# design.net
KiCad netlist of a schematic drawn in Altium Designer
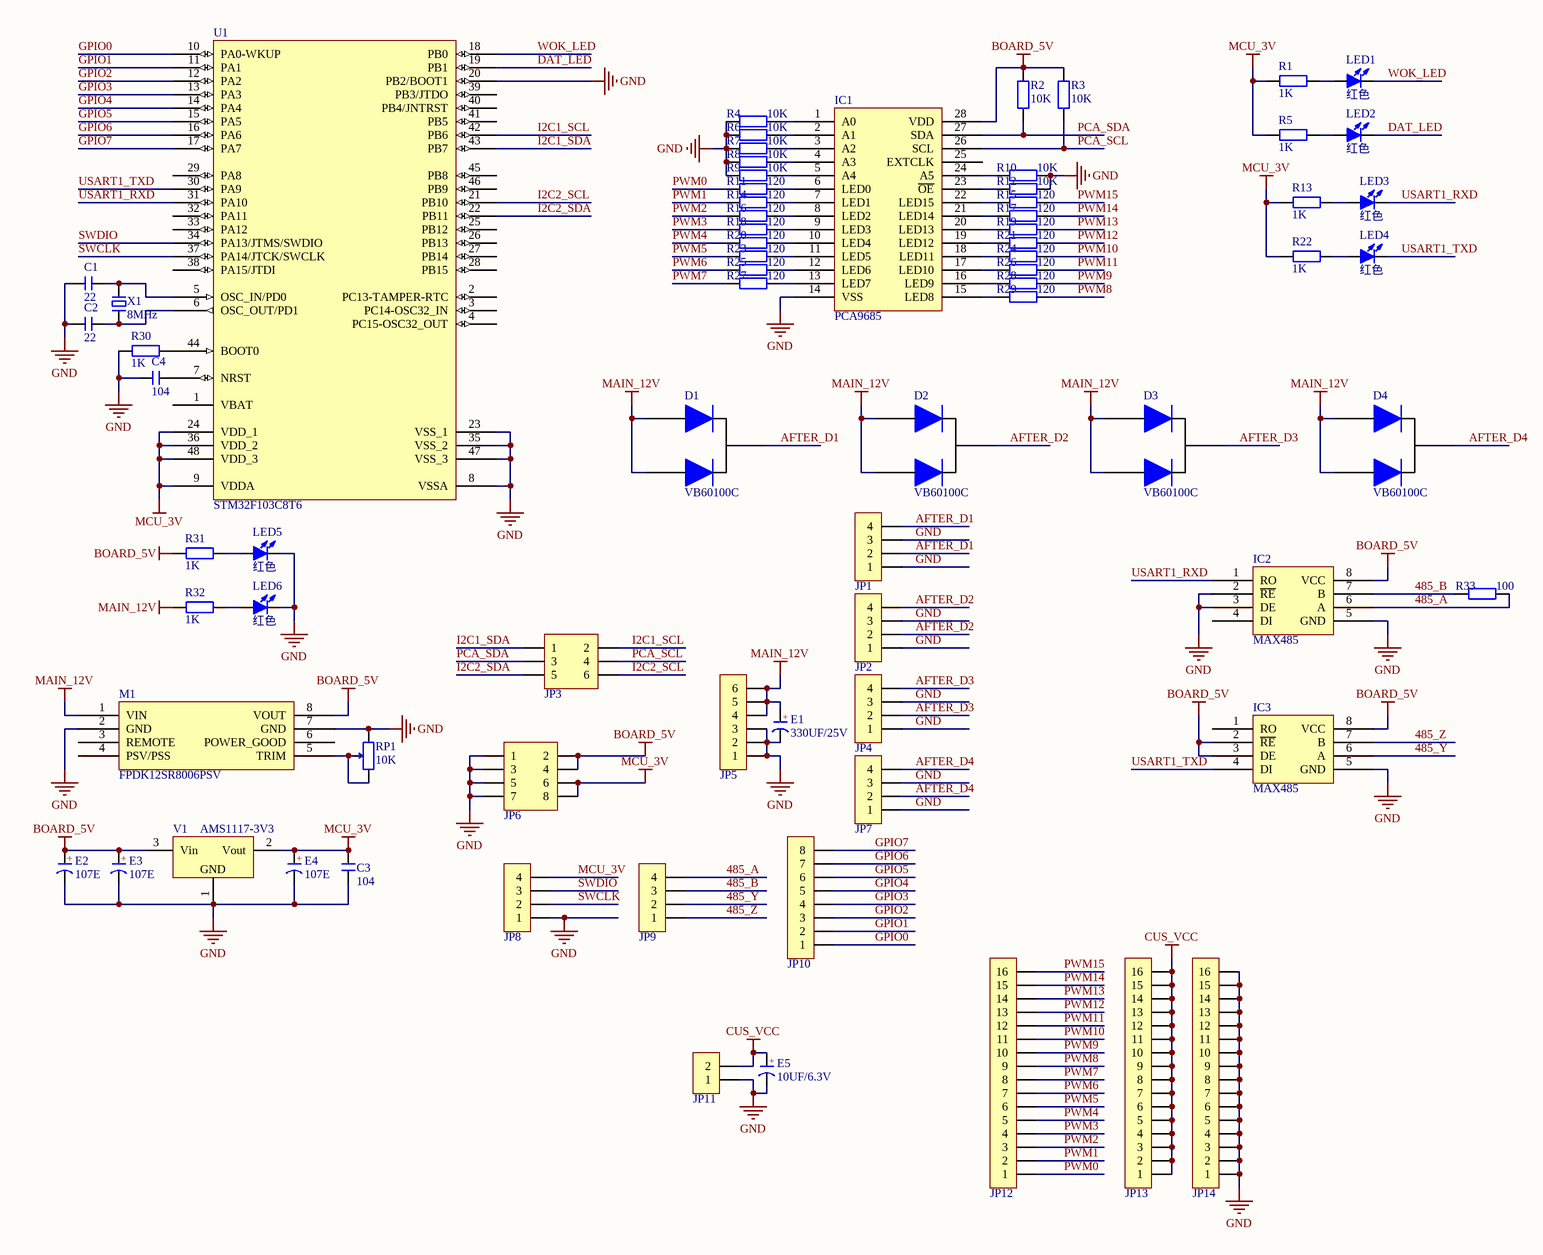
[diagram p0: 电源舱控制板.SchDoc]

(export (version "E")
  (design (tool "Eeschema 10.0.6"))
  (components
    (comp (ref "C1") (value "22") (description "无极性贴片电容") (libsource (lib "电阻-电容-电感") (part "C")))
    (comp (ref "C2") (value "22") (description "无极性贴片电容") (libsource (lib "电阻-电容-电感") (part "C")))
    (comp (ref "C3") (value "104") (description "无极性贴片电容") (libsource (lib "电阻-电容-电感") (part "C")))
    (comp (ref "C4") (value "104") (description "无极性贴片电容") (libsource (lib "电阻-电容-电感") (part "C")))
    (comp (ref "D1")
      (value "VB60100C")
      (description "60A 100V 肖特基势垒二极管")
      (libsource (lib "ROV") (part "VB60100C"))
    )
    (comp (ref "D2")
      (value "VB60100C")
      (description "60A 100V 肖特基势垒二极管")
      (libsource (lib "ROV") (part "VB60100C"))
    )
    (comp (ref "D3")
      (value "VB60100C")
      (description "60A 100V 肖特基势垒二极管")
      (libsource (lib "ROV") (part "VB60100C"))
    )
    (comp (ref "D4")
      (value "VB60100C")
      (description "60A 100V 肖特基势垒二极管")
      (libsource (lib "ROV") (part "VB60100C"))
    )
    (comp (ref "E1") (value "330UF/25V") (description "直插固态电容") (libsource (lib "电阻-电容-电感") (part "C-CS")))
    (comp (ref "E2") (value "107E") (description "贴片钽电容") (libsource (lib "电阻-电容-电感") (part "C-CD")))
    (comp (ref "E3") (value "107E") (description "贴片钽电容") (libsource (lib "电阻-电容-电感") (part "C-CD")))
    (comp (ref "E4") (value "107E") (description "贴片钽电容") (libsource (lib "电阻-电容-电感") (part "C-CD")))
    (comp (ref "E5") (value "10UF/6.3V") (description "直插固态电容") (libsource (lib "电阻-电容-电感") (part "C-CS")))
    (comp (ref "IC1") (value "PCA9685") (libsource (lib "ROV") (part "PCA9685")))
    (comp (ref "IC2") (value "MAX485") (description "485通信芯片") (libsource (lib "ROV") (part "MAX485")))
    (comp (ref "IC3") (value "MAX485") (description "485通信芯片") (libsource (lib "ROV") (part "MAX485")))
    (comp (ref "JP1") (value "HDR-1X4") (description "4P接插件") (libsource (lib "接插件") (part "Header 4")))
    (comp (ref "JP2") (value "HDR-1X4") (description "4P接插件") (libsource (lib "接插件") (part "Header 4")))
    (comp (ref "JP3") (value "Header3X2") (description "3*2P接插件") (libsource (lib "接插件") (part "Header 3X2")))
    (comp (ref "JP4") (value "HDR-1X4") (description "4P接插件") (libsource (lib "接插件") (part "Header 4")))
    (comp (ref "JP5") (value "HDR-1X6") (description "6P接插件") (libsource (lib "接插件") (part "Header 6")))
    (comp (ref "JP6")
      (value "Header 4X2")
      (description "4*2P接插件")
      (libsource (lib "接插件") (part "Header 4X2"))
    )
    (comp (ref "JP7") (value "HDR-1X4") (description "4P接插件") (libsource (lib "接插件") (part "Header 4")))
    (comp (ref "JP8") (value "HDR-1X4") (description "4P接插件") (libsource (lib "接插件") (part "Header 4")))
    (comp (ref "JP9") (value "HDR-1X4") (description "4P接插件") (libsource (lib "接插件") (part "Header 4")))
    (comp (ref "JP10") (value "HDR-1X8") (description "8P接插件") (libsource (lib "接插件") (part "Header 8")))
    (comp (ref "JP11") (value "HDR-1X2") (description "2P接插件") (libsource (lib "接插件") (part "Header 2")))
    (comp (ref "JP12") (value "HDR-1X16") (description "16P接插件") (libsource (lib "接插件") (part "Header 16")))
    (comp (ref "JP13") (value "HDR-1X16") (description "16P接插件") (libsource (lib "接插件") (part "Header 16")))
    (comp (ref "JP14") (value "HDR-1X16") (description "16P接插件") (libsource (lib "接插件") (part "Header 16")))
    (comp (ref "LED1") (value "红色") (description "贴片LED") (libsource (lib "LED") (part "LED-SMD")))
    (comp (ref "LED2") (value "红色") (description "贴片LED") (libsource (lib "LED") (part "LED-SMD")))
    (comp (ref "LED3") (value "红色") (description "贴片LED") (libsource (lib "LED") (part "LED-SMD")))
    (comp (ref "LED4") (value "红色") (description "贴片LED") (libsource (lib "LED") (part "LED-SMD")))
    (comp (ref "LED5") (value "红色") (description "贴片LED") (libsource (lib "LED") (part "LED-SMD")))
    (comp (ref "LED6") (value "红色") (description "贴片LED") (libsource (lib "LED") (part "LED-SMD")))
    (comp (ref "M1")
      (value "FPDK12SR8006PSV")
      (footprint "FPDK12SR8006PSV")
      (description "DC-DC POWER CONVERTOR 12V-TO-5V")
      (libsource (lib "ROV") (part "FPDK12SR8006PSV"))
    )
    (comp (ref "R1") (value "1K") (description "贴片电阻") (libsource (lib "电阻-电容-电感") (part "R")))
    (comp (ref "R2") (value "10K") (description "贴片电阻") (libsource (lib "电阻-电容-电感") (part "R")))
    (comp (ref "R3") (value "10K") (description "贴片电阻") (libsource (lib "电阻-电容-电感") (part "R")))
    (comp (ref "R4") (value "10K") (description "贴片电阻") (libsource (lib "电阻-电容-电感") (part "R")))
    (comp (ref "R5") (value "1K") (description "贴片电阻") (libsource (lib "电阻-电容-电感") (part "R")))
    (comp (ref "R6") (value "10K") (description "贴片电阻") (libsource (lib "电阻-电容-电感") (part "R")))
    (comp (ref "R7") (value "10K") (description "贴片电阻") (libsource (lib "电阻-电容-电感") (part "R")))
    (comp (ref "R8") (value "10K") (description "贴片电阻") (libsource (lib "电阻-电容-电感") (part "R")))
    (comp (ref "R9") (value "10K") (description "贴片电阻") (libsource (lib "电阻-电容-电感") (part "R")))
    (comp (ref "R10") (value "10K") (description "贴片电阻") (libsource (lib "电阻-电容-电感") (part "R")))
    (comp (ref "R11") (value "120") (description "贴片电阻") (libsource (lib "电阻-电容-电感") (part "R")))
    (comp (ref "R12") (value "10K") (description "贴片电阻") (libsource (lib "电阻-电容-电感") (part "R")))
    (comp (ref "R13") (value "1K") (description "贴片电阻") (libsource (lib "电阻-电容-电感") (part "R")))
    (comp (ref "R14") (value "120") (description "贴片电阻") (libsource (lib "电阻-电容-电感") (part "R")))
    (comp (ref "R15") (value "120") (description "贴片电阻") (libsource (lib "电阻-电容-电感") (part "R")))
    (comp (ref "R16") (value "120") (description "贴片电阻") (libsource (lib "电阻-电容-电感") (part "R")))
    (comp (ref "R17") (value "120") (description "贴片电阻") (libsource (lib "电阻-电容-电感") (part "R")))
    (comp (ref "R18") (value "120") (description "贴片电阻") (libsource (lib "电阻-电容-电感") (part "R")))
    (comp (ref "R19") (value "120") (description "贴片电阻") (libsource (lib "电阻-电容-电感") (part "R")))
    (comp (ref "R20") (value "120") (description "贴片电阻") (libsource (lib "电阻-电容-电感") (part "R")))
    (comp (ref "R21") (value "120") (description "贴片电阻") (libsource (lib "电阻-电容-电感") (part "R")))
    (comp (ref "R22") (value "1K") (description "贴片电阻") (libsource (lib "电阻-电容-电感") (part "R")))
    (comp (ref "R23") (value "120") (description "贴片电阻") (libsource (lib "电阻-电容-电感") (part "R")))
    (comp (ref "R24") (value "120") (description "贴片电阻") (libsource (lib "电阻-电容-电感") (part "R")))
    (comp (ref "R25") (value "120") (description "贴片电阻") (libsource (lib "电阻-电容-电感") (part "R")))
    (comp (ref "R26") (value "120") (description "贴片电阻") (libsource (lib "电阻-电容-电感") (part "R")))
    (comp (ref "R27") (value "120") (description "贴片电阻") (libsource (lib "电阻-电容-电感") (part "R")))
    (comp (ref "R28") (value "120") (description "贴片电阻") (libsource (lib "电阻-电容-电感") (part "R")))
    (comp (ref "R29") (value "120") (description "贴片电阻") (libsource (lib "电阻-电容-电感") (part "R")))
    (comp (ref "R30") (value "1K") (description "贴片电阻") (libsource (lib "电阻-电容-电感") (part "R")))
    (comp (ref "R31") (value "1K") (description "贴片电阻") (libsource (lib "电阻-电容-电感") (part "R")))
    (comp (ref "R32") (value "1K") (description "贴片电阻") (libsource (lib "电阻-电容-电感") (part "R")))
    (comp (ref "R33") (value "100") (description "贴片电阻") (libsource (lib "电阻-电容-电感") (part "R")))
    (comp (ref "RP1")
      (value "10K")
      (footprint "3296W")
      (description "插件单联电位器")
      (libsource (lib "电阻-电容-电感") (part "RP-ID"))
    )
    (comp (ref "U1")
      (value "STM32F103C8T6")
      (description "Flaah:64/RAM:20/IO:36")
      (libsource (lib "STM32系列单片机") (part "STM32F103C8T6"))
    )
    (comp (ref "V1") (value "AMS1117-3V3") (description "三端稳压芯片") (libsource (lib "IC芯片") (part "AMS1117")))
    (comp (ref "X1")
      (value "8MHz")
      (footprint "XTAL-49S DIP")
      (description "2脚晶振")
      (libsource (lib "保险丝-晶振") (part "XTAL-2"))
    )
  )
  (nets
    (net (code "1") (name "/485_A") (class "Default")
      (node (ref "IC2") (pin "6") (pinfunction "A_6") (pintype "passive"))
      (node (ref "JP9") (pin "4") (pinfunction "4_4") (pintype "passive"))
      (node (ref "R33") (pin "2") (pinfunction "2_2") (pintype "passive"))
    )
    (net (code "2") (name "/485_B") (class "Default")
      (node (ref "IC2") (pin "7") (pinfunction "B_7") (pintype "passive"))
      (node (ref "JP9") (pin "3") (pinfunction "3_3") (pintype "passive"))
      (node (ref "R33") (pin "1") (pinfunction "1_1") (pintype "passive"))
    )
    (net (code "3") (name "/485_Y") (class "Default")
      (node (ref "IC3") (pin "6") (pinfunction "A_6") (pintype "passive"))
      (node (ref "JP9") (pin "2") (pinfunction "2_2") (pintype "passive"))
    )
    (net (code "4") (name "/485_Z") (class "Default")
      (node (ref "IC3") (pin "7") (pinfunction "B_7") (pintype "passive"))
      (node (ref "JP9") (pin "1") (pinfunction "1_1") (pintype "passive"))
    )
    (net (code "5") (name "/AFTER_D1") (class "Default")
      (node (ref "D1") (pin "2") (pinfunction "2_2") (pintype "passive"))
      (node (ref "JP1") (pin "2") (pinfunction "2_2") (pintype "passive"))
      (node (ref "JP1") (pin "4") (pinfunction "4_4") (pintype "passive"))
    )
    (net (code "6") (name "/AFTER_D2") (class "Default")
      (node (ref "D2") (pin "2") (pinfunction "2_2") (pintype "passive"))
      (node (ref "JP2") (pin "2") (pinfunction "2_2") (pintype "passive"))
      (node (ref "JP2") (pin "4") (pinfunction "4_4") (pintype "passive"))
    )
    (net (code "7") (name "/AFTER_D3") (class "Default")
      (node (ref "D3") (pin "2") (pinfunction "2_2") (pintype "passive"))
      (node (ref "JP4") (pin "2") (pinfunction "2_2") (pintype "passive"))
      (node (ref "JP4") (pin "4") (pinfunction "4_4") (pintype "passive"))
    )
    (net (code "8") (name "/AFTER_D4") (class "Default")
      (node (ref "D4") (pin "2") (pinfunction "2_2") (pintype "passive"))
      (node (ref "JP7") (pin "2") (pinfunction "2_2") (pintype "passive"))
      (node (ref "JP7") (pin "4") (pinfunction "4_4") (pintype "passive"))
    )
    (net (code "9") (name "/DAT_LED") (class "Default")
      (node (ref "LED2") (pin "2") (pinfunction "K_2") (pintype "passive"))
      (node (ref "U1") (pin "19") (pinfunction "PB1_19") (pintype "bidirectional"))
    )
    (net (code "10") (name "/GPIO0") (class "Default")
      (node (ref "JP10") (pin "1") (pinfunction "1_1") (pintype "passive"))
      (node (ref "U1") (pin "10") (pinfunction "PA0-WKUP_10") (pintype "bidirectional"))
    )
    (net (code "11") (name "/GPIO1") (class "Default")
      (node (ref "JP10") (pin "2") (pinfunction "2_2") (pintype "passive"))
      (node (ref "U1") (pin "11") (pinfunction "PA1_11") (pintype "bidirectional"))
    )
    (net (code "12") (name "/GPIO2") (class "Default")
      (node (ref "JP10") (pin "3") (pinfunction "3_3") (pintype "passive"))
      (node (ref "U1") (pin "12") (pinfunction "PA2_12") (pintype "bidirectional"))
    )
    (net (code "13") (name "/GPIO3") (class "Default")
      (node (ref "JP10") (pin "4") (pinfunction "4_4") (pintype "passive"))
      (node (ref "U1") (pin "13") (pinfunction "PA3_13") (pintype "bidirectional"))
    )
    (net (code "14") (name "/GPIO4") (class "Default")
      (node (ref "JP10") (pin "5") (pinfunction "5_5") (pintype "passive"))
      (node (ref "U1") (pin "14") (pinfunction "PA4_14") (pintype "bidirectional"))
    )
    (net (code "15") (name "/GPIO5") (class "Default")
      (node (ref "JP10") (pin "6") (pinfunction "6_6") (pintype "passive"))
      (node (ref "U1") (pin "15") (pinfunction "PA5_15") (pintype "bidirectional"))
    )
    (net (code "16") (name "/GPIO6") (class "Default")
      (node (ref "JP10") (pin "7") (pinfunction "7_7") (pintype "passive"))
      (node (ref "U1") (pin "16") (pinfunction "PA6_16") (pintype "bidirectional"))
    )
    (net (code "17") (name "/GPIO7") (class "Default")
      (node (ref "JP10") (pin "8") (pinfunction "8_8") (pintype "passive"))
      (node (ref "U1") (pin "17") (pinfunction "PA7_17") (pintype "bidirectional"))
    )
    (net (code "18") (name "/I2C1_SCL") (class "Default")
      (node (ref "JP3") (pin "2") (pinfunction "2_2") (pintype "passive"))
      (node (ref "U1") (pin "42") (pinfunction "PB6_42") (pintype "bidirectional"))
    )
    (net (code "19") (name "/I2C1_SDA") (class "Default")
      (node (ref "JP3") (pin "1") (pinfunction "1_1") (pintype "passive"))
      (node (ref "U1") (pin "43") (pinfunction "PB7_43") (pintype "bidirectional"))
    )
    (net (code "20") (name "/I2C2_SCL") (class "Default")
      (node (ref "JP3") (pin "6") (pinfunction "6_6") (pintype "passive"))
      (node (ref "U1") (pin "21") (pinfunction "PB10_21") (pintype "bidirectional"))
    )
    (net (code "21") (name "/I2C2_SDA") (class "Default")
      (node (ref "JP3") (pin "5") (pinfunction "5_5") (pintype "passive"))
      (node (ref "U1") (pin "22") (pinfunction "PB11_22") (pintype "bidirectional"))
    )
    (net (code "22") (name "/PCA_SCL") (class "Default")
      (node (ref "IC1") (pin "26") (pinfunction "SCL_26") (pintype "passive"))
      (node (ref "JP3") (pin "4") (pinfunction "4_4") (pintype "passive"))
      (node (ref "R3") (pin "1") (pinfunction "1_1") (pintype "passive"))
    )
    (net (code "23") (name "/PCA_SDA") (class "Default")
      (node (ref "IC1") (pin "27") (pinfunction "SDA_27") (pintype "passive"))
      (node (ref "JP3") (pin "3") (pinfunction "3_3") (pintype "passive"))
      (node (ref "R2") (pin "1") (pinfunction "1_1") (pintype "passive"))
    )
    (net (code "24") (name "/PWM0") (class "Default")
      (node (ref "JP12") (pin "1") (pinfunction "1_1") (pintype "passive"))
      (node (ref "R11") (pin "1") (pinfunction "1_1") (pintype "passive"))
    )
    (net (code "25") (name "/PWM1") (class "Default")
      (node (ref "JP12") (pin "2") (pinfunction "2_2") (pintype "passive"))
      (node (ref "R14") (pin "1") (pinfunction "1_1") (pintype "passive"))
    )
    (net (code "26") (name "/PWM2") (class "Default")
      (node (ref "JP12") (pin "3") (pinfunction "3_3") (pintype "passive"))
      (node (ref "R16") (pin "1") (pinfunction "1_1") (pintype "passive"))
    )
    (net (code "27") (name "/PWM3") (class "Default")
      (node (ref "JP12") (pin "4") (pinfunction "4_4") (pintype "passive"))
      (node (ref "R18") (pin "1") (pinfunction "1_1") (pintype "passive"))
    )
    (net (code "28") (name "/PWM4") (class "Default")
      (node (ref "JP12") (pin "5") (pinfunction "5_5") (pintype "passive"))
      (node (ref "R20") (pin "1") (pinfunction "1_1") (pintype "passive"))
    )
    (net (code "29") (name "/PWM5") (class "Default")
      (node (ref "JP12") (pin "6") (pinfunction "6_6") (pintype "passive"))
      (node (ref "R23") (pin "1") (pinfunction "1_1") (pintype "passive"))
    )
    (net (code "30") (name "/PWM6") (class "Default")
      (node (ref "JP12") (pin "7") (pinfunction "7_7") (pintype "passive"))
      (node (ref "R25") (pin "1") (pinfunction "1_1") (pintype "passive"))
    )
    (net (code "31") (name "/PWM7") (class "Default")
      (node (ref "JP12") (pin "8") (pinfunction "8_8") (pintype "passive"))
      (node (ref "R27") (pin "1") (pinfunction "1_1") (pintype "passive"))
    )
    (net (code "32") (name "/PWM8") (class "Default")
      (node (ref "JP12") (pin "9") (pinfunction "9_9") (pintype "passive"))
      (node (ref "R29") (pin "2") (pinfunction "2_2") (pintype "passive"))
    )
    (net (code "33") (name "/PWM9") (class "Default")
      (node (ref "JP12") (pin "10") (pinfunction "10_10") (pintype "passive"))
      (node (ref "R28") (pin "2") (pinfunction "2_2") (pintype "passive"))
    )
    (net (code "34") (name "/PWM10") (class "Default")
      (node (ref "JP12") (pin "11") (pinfunction "11_11") (pintype "passive"))
      (node (ref "R24") (pin "2") (pinfunction "2_2") (pintype "passive"))
    )
    (net (code "35") (name "/PWM11") (class "Default")
      (node (ref "JP12") (pin "12") (pinfunction "12_12") (pintype "passive"))
      (node (ref "R26") (pin "2") (pinfunction "2_2") (pintype "passive"))
    )
    (net (code "36") (name "/PWM12") (class "Default")
      (node (ref "JP12") (pin "13") (pinfunction "13_13") (pintype "passive"))
      (node (ref "R21") (pin "2") (pinfunction "2_2") (pintype "passive"))
    )
    (net (code "37") (name "/PWM13") (class "Default")
      (node (ref "JP12") (pin "14") (pinfunction "14_14") (pintype "passive"))
      (node (ref "R19") (pin "2") (pinfunction "2_2") (pintype "passive"))
    )
    (net (code "38") (name "/PWM14") (class "Default")
      (node (ref "JP12") (pin "15") (pinfunction "15_15") (pintype "passive"))
      (node (ref "R17") (pin "2") (pinfunction "2_2") (pintype "passive"))
    )
    (net (code "39") (name "/PWM15") (class "Default")
      (node (ref "JP12") (pin "16") (pinfunction "16_16") (pintype "passive"))
      (node (ref "R15") (pin "2") (pinfunction "2_2") (pintype "passive"))
    )
    (net (code "40") (name "/SWCLK") (class "Default")
      (node (ref "JP8") (pin "2") (pinfunction "2_2") (pintype "passive"))
      (node (ref "U1") (pin "37") (pinfunction "PA14/JTCK/SWCLK_37") (pintype "bidirectional"))
    )
    (net (code "41") (name "/SWDIO") (class "Default")
      (node (ref "JP8") (pin "3") (pinfunction "3_3") (pintype "passive"))
      (node (ref "U1") (pin "34") (pinfunction "PA13/JTMS/SWDIO_34") (pintype "bidirectional"))
    )
    (net (code "42") (name "/USART1_RXD") (class "Default")
      (node (ref "IC2") (pin "1") (pinfunction "RO_1") (pintype "passive"))
      (node (ref "LED3") (pin "2") (pinfunction "K_2") (pintype "passive"))
      (node (ref "U1") (pin "31") (pinfunction "PA10_31") (pintype "bidirectional"))
    )
    (net (code "43") (name "/USART1_TXD") (class "Default")
      (node (ref "IC3") (pin "4") (pinfunction "DI_4") (pintype "passive"))
      (node (ref "LED4") (pin "2") (pinfunction "K_2") (pintype "passive"))
      (node (ref "U1") (pin "30") (pinfunction "PA9_30") (pintype "bidirectional"))
    )
    (net (code "44") (name "/WOK_LED") (class "Default")
      (node (ref "LED1") (pin "2") (pinfunction "K_2") (pintype "passive"))
      (node (ref "U1") (pin "18") (pinfunction "PB0_18") (pintype "bidirectional"))
    )
    (net (code "45") (name "BOARD_5V") (class "Default")
      (node (ref "E2") (pin "1") (pinfunction "A_1") (pintype "passive"))
      (node (ref "E3") (pin "1") (pinfunction "A_1") (pintype "passive"))
      (node (ref "IC1") (pin "28") (pinfunction "VDD_28") (pintype "passive"))
      (node (ref "IC2") (pin "8") (pinfunction "VCC_8") (pintype "passive"))
      (node (ref "IC3") (pin "2") (pinfunction "~{RE}_2") (pintype "passive"))
      (node (ref "IC3") (pin "3") (pinfunction "DE_3") (pintype "passive"))
      (node (ref "IC3") (pin "8") (pinfunction "VCC_8") (pintype "passive"))
      (node (ref "JP6") (pin "2") (pinfunction "2_2") (pintype "passive"))
      (node (ref "JP6") (pin "4") (pinfunction "4_4") (pintype "passive"))
      (node (ref "M1") (pin "8") (pinfunction "VOUT_8") (pintype "passive"))
      (node (ref "R2") (pin "2") (pinfunction "2_2") (pintype "passive"))
      (node (ref "R3") (pin "2") (pinfunction "2_2") (pintype "passive"))
      (node (ref "R31") (pin "1") (pinfunction "1_1") (pintype "passive"))
      (node (ref "V1") (pin "3") (pinfunction "Vin_3") (pintype "passive"))
    )
    (net (code "46") (name "CUS_VCC") (class "Default")
      (node (ref "E5") (pin "1") (pinfunction "A_1") (pintype "passive"))
      (node (ref "JP11") (pin "2") (pinfunction "2_2") (pintype "passive"))
      (node (ref "JP13") (pin "1") (pinfunction "1_1") (pintype "passive"))
      (node (ref "JP13") (pin "10") (pinfunction "10_10") (pintype "passive"))
      (node (ref "JP13") (pin "11") (pinfunction "11_11") (pintype "passive"))
      (node (ref "JP13") (pin "12") (pinfunction "12_12") (pintype "passive"))
      (node (ref "JP13") (pin "13") (pinfunction "13_13") (pintype "passive"))
      (node (ref "JP13") (pin "14") (pinfunction "14_14") (pintype "passive"))
      (node (ref "JP13") (pin "15") (pinfunction "15_15") (pintype "passive"))
      (node (ref "JP13") (pin "16") (pinfunction "16_16") (pintype "passive"))
      (node (ref "JP13") (pin "2") (pinfunction "2_2") (pintype "passive"))
      (node (ref "JP13") (pin "3") (pinfunction "3_3") (pintype "passive"))
      (node (ref "JP13") (pin "4") (pinfunction "4_4") (pintype "passive"))
      (node (ref "JP13") (pin "5") (pinfunction "5_5") (pintype "passive"))
      (node (ref "JP13") (pin "6") (pinfunction "6_6") (pintype "passive"))
      (node (ref "JP13") (pin "7") (pinfunction "7_7") (pintype "passive"))
      (node (ref "JP13") (pin "8") (pinfunction "8_8") (pintype "passive"))
      (node (ref "JP13") (pin "9") (pinfunction "9_9") (pintype "passive"))
    )
    (net (code "47") (name "GND") (class "Default")
      (node (ref "C1") (pin "1") (pinfunction "1_1") (pintype "passive"))
      (node (ref "C2") (pin "1") (pinfunction "1_1") (pintype "passive"))
      (node (ref "C3") (pin "1") (pinfunction "1_1") (pintype "passive"))
      (node (ref "C4") (pin "1") (pinfunction "1_1") (pintype "passive"))
      (node (ref "E1") (pin "2") (pinfunction "K_2") (pintype "passive"))
      (node (ref "E2") (pin "2") (pinfunction "K_2") (pintype "passive"))
      (node (ref "E3") (pin "2") (pinfunction "K_2") (pintype "passive"))
      (node (ref "E4") (pin "2") (pinfunction "K_2") (pintype "passive"))
      (node (ref "E5") (pin "2") (pinfunction "K_2") (pintype "passive"))
      (node (ref "IC1") (pin "14") (pinfunction "VSS_14") (pintype "passive"))
      (node (ref "IC2") (pin "2") (pinfunction "~{RE}_2") (pintype "passive"))
      (node (ref "IC2") (pin "3") (pinfunction "DE_3") (pintype "passive"))
      (node (ref "IC2") (pin "5") (pinfunction "GND_5") (pintype "passive"))
      (node (ref "IC3") (pin "5") (pinfunction "GND_5") (pintype "passive"))
      (node (ref "JP1") (pin "1") (pinfunction "1_1") (pintype "passive"))
      (node (ref "JP1") (pin "3") (pinfunction "3_3") (pintype "passive"))
      (node (ref "JP11") (pin "1") (pinfunction "1_1") (pintype "passive"))
      (node (ref "JP14") (pin "1") (pinfunction "1_1") (pintype "passive"))
      (node (ref "JP14") (pin "10") (pinfunction "10_10") (pintype "passive"))
      (node (ref "JP14") (pin "11") (pinfunction "11_11") (pintype "passive"))
      (node (ref "JP14") (pin "12") (pinfunction "12_12") (pintype "passive"))
      (node (ref "JP14") (pin "13") (pinfunction "13_13") (pintype "passive"))
      (node (ref "JP14") (pin "14") (pinfunction "14_14") (pintype "passive"))
      (node (ref "JP14") (pin "15") (pinfunction "15_15") (pintype "passive"))
      (node (ref "JP14") (pin "16") (pinfunction "16_16") (pintype "passive"))
      (node (ref "JP14") (pin "2") (pinfunction "2_2") (pintype "passive"))
      (node (ref "JP14") (pin "3") (pinfunction "3_3") (pintype "passive"))
      (node (ref "JP14") (pin "4") (pinfunction "4_4") (pintype "passive"))
      (node (ref "JP14") (pin "5") (pinfunction "5_5") (pintype "passive"))
      (node (ref "JP14") (pin "6") (pinfunction "6_6") (pintype "passive"))
      (node (ref "JP14") (pin "7") (pinfunction "7_7") (pintype "passive"))
      (node (ref "JP14") (pin "8") (pinfunction "8_8") (pintype "passive"))
      (node (ref "JP14") (pin "9") (pinfunction "9_9") (pintype "passive"))
      (node (ref "JP2") (pin "1") (pinfunction "1_1") (pintype "passive"))
      (node (ref "JP2") (pin "3") (pinfunction "3_3") (pintype "passive"))
      (node (ref "JP4") (pin "1") (pinfunction "1_1") (pintype "passive"))
      (node (ref "JP4") (pin "3") (pinfunction "3_3") (pintype "passive"))
      (node (ref "JP5") (pin "1") (pinfunction "1_1") (pintype "passive"))
      (node (ref "JP5") (pin "2") (pinfunction "2_2") (pintype "passive"))
      (node (ref "JP5") (pin "3") (pinfunction "3_3") (pintype "passive"))
      (node (ref "JP6") (pin "1") (pinfunction "1_1") (pintype "passive"))
      (node (ref "JP6") (pin "3") (pinfunction "3_3") (pintype "passive"))
      (node (ref "JP6") (pin "5") (pinfunction "5_5") (pintype "passive"))
      (node (ref "JP6") (pin "7") (pinfunction "7_7") (pintype "passive"))
      (node (ref "JP7") (pin "1") (pinfunction "1_1") (pintype "passive"))
      (node (ref "JP7") (pin "3") (pinfunction "3_3") (pintype "passive"))
      (node (ref "JP8") (pin "1") (pinfunction "1_1") (pintype "passive"))
      (node (ref "LED5") (pin "2") (pinfunction "K_2") (pintype "passive"))
      (node (ref "LED6") (pin "2") (pinfunction "K_2") (pintype "passive"))
      (node (ref "M1") (pin "2") (pinfunction "GND_2") (pintype "passive"))
      (node (ref "M1") (pin "7") (pinfunction "GND_7") (pintype "passive"))
      (node (ref "R10") (pin "2") (pinfunction "2_2") (pintype "passive"))
      (node (ref "R12") (pin "2") (pinfunction "2_2") (pintype "passive"))
      (node (ref "R30") (pin "2") (pinfunction "2_2") (pintype "passive"))
      (node (ref "R4") (pin "1") (pinfunction "1_1") (pintype "passive"))
      (node (ref "R6") (pin "1") (pinfunction "1_1") (pintype "passive"))
      (node (ref "R7") (pin "1") (pinfunction "1_1") (pintype "passive"))
      (node (ref "R8") (pin "1") (pinfunction "1_1") (pintype "passive"))
      (node (ref "R9") (pin "1") (pinfunction "1_1") (pintype "passive"))
      (node (ref "RP1") (pin "3") (pinfunction "3_3") (pintype "passive"))
      (node (ref "U1") (pin "20") (pinfunction "PB2/BOOT1_20") (pintype "bidirectional"))
      (node (ref "U1") (pin "23") (pinfunction "VSS_1_23") (pintype "power_in"))
      (node (ref "U1") (pin "35") (pinfunction "VSS_2_35") (pintype "power_in"))
      (node (ref "U1") (pin "47") (pinfunction "VSS_3_47") (pintype "power_in"))
      (node (ref "U1") (pin "8") (pinfunction "VSSA_8") (pintype "power_in"))
      (node (ref "V1") (pin "1") (pinfunction "GND_1") (pintype "passive"))
    )
    (net (code "48") (name "MAIN_12V") (class "Default")
      (node (ref "D1") (pin "1") (pintype "passive"))
      (node (ref "D1") (pin "3") (pintype "passive"))
      (node (ref "D2") (pin "1") (pintype "passive"))
      (node (ref "D2") (pin "3") (pintype "passive"))
      (node (ref "D3") (pin "1") (pintype "passive"))
      (node (ref "D3") (pin "3") (pintype "passive"))
      (node (ref "D4") (pin "1") (pintype "passive"))
      (node (ref "D4") (pin "3") (pintype "passive"))
      (node (ref "E1") (pin "1") (pinfunction "A_1") (pintype "passive"))
      (node (ref "JP5") (pin "4") (pinfunction "4_4") (pintype "passive"))
      (node (ref "JP5") (pin "5") (pinfunction "5_5") (pintype "passive"))
      (node (ref "JP5") (pin "6") (pinfunction "6_6") (pintype "passive"))
      (node (ref "M1") (pin "1") (pinfunction "VIN_1") (pintype "passive"))
      (node (ref "R32") (pin "1") (pinfunction "1_1") (pintype "passive"))
    )
    (net (code "49") (name "MCU_3V") (class "Default")
      (node (ref "C3") (pin "2") (pinfunction "2_2") (pintype "passive"))
      (node (ref "E4") (pin "1") (pinfunction "A_1") (pintype "passive"))
      (node (ref "JP6") (pin "6") (pinfunction "6_6") (pintype "passive"))
      (node (ref "JP6") (pin "8") (pinfunction "8_8") (pintype "passive"))
      (node (ref "JP8") (pin "4") (pinfunction "4_4") (pintype "passive"))
      (node (ref "R1") (pin "1") (pinfunction "1_1") (pintype "passive"))
      (node (ref "R13") (pin "1") (pinfunction "1_1") (pintype "passive"))
      (node (ref "R22") (pin "1") (pinfunction "1_1") (pintype "passive"))
      (node (ref "R5") (pin "1") (pinfunction "1_1") (pintype "passive"))
      (node (ref "U1") (pin "24") (pinfunction "VDD_1_24") (pintype "power_in"))
      (node (ref "U1") (pin "36") (pinfunction "VDD_2_36") (pintype "power_in"))
      (node (ref "U1") (pin "48") (pinfunction "VDD_3_48") (pintype "power_in"))
      (node (ref "U1") (pin "9") (pinfunction "VDDA_9") (pintype "power_in"))
      (node (ref "V1") (pin "2") (pinfunction "Vout_2") (pintype "passive"))
    )
    (net (code "50") (name "Net-(IC1-A0)") (class "Default")
      (node (ref "IC1") (pin "1") (pinfunction "A0_1") (pintype "passive"))
      (node (ref "R4") (pin "2") (pinfunction "2_2") (pintype "passive"))
    )
    (net (code "51") (name "Net-(IC1-A1)") (class "Default")
      (node (ref "IC1") (pin "2") (pinfunction "A1_2") (pintype "passive"))
      (node (ref "R6") (pin "2") (pinfunction "2_2") (pintype "passive"))
    )
    (net (code "52") (name "Net-(IC1-A2)") (class "Default")
      (node (ref "IC1") (pin "3") (pinfunction "A2_3") (pintype "passive"))
      (node (ref "R7") (pin "2") (pinfunction "2_2") (pintype "passive"))
    )
    (net (code "53") (name "Net-(IC1-A3)") (class "Default")
      (node (ref "IC1") (pin "4") (pinfunction "A3_4") (pintype "passive"))
      (node (ref "R8") (pin "2") (pinfunction "2_2") (pintype "passive"))
    )
    (net (code "54") (name "Net-(IC1-A4)") (class "Default")
      (node (ref "IC1") (pin "5") (pinfunction "A4_5") (pintype "passive"))
      (node (ref "R9") (pin "2") (pinfunction "2_2") (pintype "passive"))
    )
    (net (code "55") (name "Net-(IC1-A5)") (class "Default")
      (node (ref "IC1") (pin "24") (pinfunction "A5_24") (pintype "passive"))
      (node (ref "R10") (pin "1") (pinfunction "1_1") (pintype "passive"))
    )
    (net (code "56") (name "Net-(IC1-LED0)") (class "Default")
      (node (ref "IC1") (pin "6") (pinfunction "LED0_6") (pintype "passive"))
      (node (ref "R11") (pin "2") (pinfunction "2_2") (pintype "passive"))
    )
    (net (code "57") (name "Net-(IC1-LED1)") (class "Default")
      (node (ref "IC1") (pin "7") (pinfunction "LED1_7") (pintype "passive"))
      (node (ref "R14") (pin "2") (pinfunction "2_2") (pintype "passive"))
    )
    (net (code "58") (name "Net-(IC1-LED2)") (class "Default")
      (node (ref "IC1") (pin "8") (pinfunction "LED2_8") (pintype "passive"))
      (node (ref "R16") (pin "2") (pinfunction "2_2") (pintype "passive"))
    )
    (net (code "59") (name "Net-(IC1-LED3)") (class "Default")
      (node (ref "IC1") (pin "9") (pinfunction "LED3_9") (pintype "passive"))
      (node (ref "R18") (pin "2") (pinfunction "2_2") (pintype "passive"))
    )
    (net (code "60") (name "Net-(IC1-LED4)") (class "Default")
      (node (ref "IC1") (pin "10") (pinfunction "LED4_10") (pintype "passive"))
      (node (ref "R20") (pin "2") (pinfunction "2_2") (pintype "passive"))
    )
    (net (code "61") (name "Net-(IC1-LED5)") (class "Default")
      (node (ref "IC1") (pin "11") (pinfunction "LED5_11") (pintype "passive"))
      (node (ref "R23") (pin "2") (pinfunction "2_2") (pintype "passive"))
    )
    (net (code "62") (name "Net-(IC1-LED6)") (class "Default")
      (node (ref "IC1") (pin "12") (pinfunction "LED6_12") (pintype "passive"))
      (node (ref "R25") (pin "2") (pinfunction "2_2") (pintype "passive"))
    )
    (net (code "63") (name "Net-(IC1-LED7)") (class "Default")
      (node (ref "IC1") (pin "13") (pinfunction "LED7_13") (pintype "passive"))
      (node (ref "R27") (pin "2") (pinfunction "2_2") (pintype "passive"))
    )
    (net (code "64") (name "Net-(IC1-LED8)") (class "Default")
      (node (ref "IC1") (pin "15") (pinfunction "LED8_15") (pintype "passive"))
      (node (ref "R29") (pin "1") (pinfunction "1_1") (pintype "passive"))
    )
    (net (code "65") (name "Net-(IC1-LED9)") (class "Default")
      (node (ref "IC1") (pin "16") (pinfunction "LED9_16") (pintype "passive"))
      (node (ref "R28") (pin "1") (pinfunction "1_1") (pintype "passive"))
    )
    (net (code "66") (name "Net-(IC1-LED10)") (class "Default")
      (node (ref "IC1") (pin "17") (pinfunction "LED10_17") (pintype "passive"))
      (node (ref "R26") (pin "1") (pinfunction "1_1") (pintype "passive"))
    )
    (net (code "67") (name "Net-(IC1-LED11)") (class "Default")
      (node (ref "IC1") (pin "18") (pinfunction "LED11_18") (pintype "passive"))
      (node (ref "R24") (pin "1") (pinfunction "1_1") (pintype "passive"))
    )
    (net (code "68") (name "Net-(IC1-LED12)") (class "Default")
      (node (ref "IC1") (pin "19") (pinfunction "LED12_19") (pintype "passive"))
      (node (ref "R21") (pin "1") (pinfunction "1_1") (pintype "passive"))
    )
    (net (code "69") (name "Net-(IC1-LED13)") (class "Default")
      (node (ref "IC1") (pin "20") (pinfunction "LED13_20") (pintype "passive"))
      (node (ref "R19") (pin "1") (pinfunction "1_1") (pintype "passive"))
    )
    (net (code "70") (name "Net-(IC1-LED14)") (class "Default")
      (node (ref "IC1") (pin "21") (pinfunction "LED14_21") (pintype "passive"))
      (node (ref "R17") (pin "1") (pinfunction "1_1") (pintype "passive"))
    )
    (net (code "71") (name "Net-(IC1-LED15)") (class "Default")
      (node (ref "IC1") (pin "22") (pinfunction "LED15_22") (pintype "passive"))
      (node (ref "R15") (pin "1") (pinfunction "1_1") (pintype "passive"))
    )
    (net (code "72") (name "Net-(IC1-~{OE})") (class "Default")
      (node (ref "IC1") (pin "23") (pinfunction "~{OE}_23") (pintype "passive"))
      (node (ref "R12") (pin "1") (pinfunction "1_1") (pintype "passive"))
    )
    (net (code "73") (name "Net-(LED1-A)") (class "Default")
      (node (ref "LED1") (pin "1") (pinfunction "A_1") (pintype "passive"))
      (node (ref "R1") (pin "2") (pinfunction "2_2") (pintype "passive"))
    )
    (net (code "74") (name "Net-(LED2-A)") (class "Default")
      (node (ref "LED2") (pin "1") (pinfunction "A_1") (pintype "passive"))
      (node (ref "R5") (pin "2") (pinfunction "2_2") (pintype "passive"))
    )
    (net (code "75") (name "Net-(LED3-A)") (class "Default")
      (node (ref "LED3") (pin "1") (pinfunction "A_1") (pintype "passive"))
      (node (ref "R13") (pin "2") (pinfunction "2_2") (pintype "passive"))
    )
    (net (code "76") (name "Net-(LED4-A)") (class "Default")
      (node (ref "LED4") (pin "1") (pinfunction "A_1") (pintype "passive"))
      (node (ref "R22") (pin "2") (pinfunction "2_2") (pintype "passive"))
    )
    (net (code "77") (name "Net-(LED5-A)") (class "Default")
      (node (ref "LED5") (pin "1") (pinfunction "A_1") (pintype "passive"))
      (node (ref "R31") (pin "2") (pinfunction "2_2") (pintype "passive"))
    )
    (net (code "78") (name "Net-(LED6-A)") (class "Default")
      (node (ref "LED6") (pin "1") (pinfunction "A_1") (pintype "passive"))
      (node (ref "R32") (pin "2") (pinfunction "2_2") (pintype "passive"))
    )
    (net (code "79") (name "Net-(M1-TRIM)") (class "Default")
      (node (ref "M1") (pin "5") (pinfunction "TRIM_5") (pintype "passive"))
      (node (ref "RP1") (pin "1") (pinfunction "1_1") (pintype "passive"))
      (node (ref "RP1") (pin "2") (pinfunction "2_2") (pintype "passive"))
    )
    (net (code "80") (name "Net-(U1-BOOT0)") (class "Default")
      (node (ref "R30") (pin "1") (pinfunction "1_1") (pintype "passive"))
      (node (ref "U1") (pin "44") (pinfunction "BOOT0_44") (pintype "input"))
    )
    (net (code "81") (name "Net-(U1-NRST)") (class "Default")
      (node (ref "C4") (pin "2") (pinfunction "2_2") (pintype "passive"))
      (node (ref "U1") (pin "7") (pinfunction "NRST_7") (pintype "bidirectional"))
    )
    (net (code "82") (name "Net-(U1-OSC_IN{slash}PD0)") (class "Default")
      (node (ref "C1") (pin "2") (pinfunction "2_2") (pintype "passive"))
      (node (ref "U1") (pin "5") (pinfunction "OSC_IN/PD0_5") (pintype "input"))
      (node (ref "X1") (pin "2") (pinfunction "2_2") (pintype "passive"))
    )
    (net (code "83") (name "Net-(U1-OSC_OUT{slash}PD1)") (class "Default")
      (node (ref "C2") (pin "2") (pinfunction "2_2") (pintype "passive"))
      (node (ref "U1") (pin "6") (pinfunction "OSC_OUT/PD1_6") (pintype "output"))
      (node (ref "X1") (pin "1") (pinfunction "1_1") (pintype "passive"))
    )
    (net (code "84") (name "unconnected-(IC1-EXTCLK-Pad25)") (class "Default")
      (node (ref "IC1") (pin "25") (pinfunction "EXTCLK_25") (pintype "passive"))
    )
    (net (code "85") (name "unconnected-(IC2-DI-Pad4)") (class "Default")
      (node (ref "IC2") (pin "4") (pinfunction "DI_4") (pintype "passive"))
    )
    (net (code "86") (name "unconnected-(IC3-RO-Pad1)") (class "Default")
      (node (ref "IC3") (pin "1") (pinfunction "RO_1") (pintype "passive"))
    )
    (net (code "87") (name "unconnected-(M1-POWER_GOOD-Pad6)") (class "Default")
      (node (ref "M1") (pin "6") (pinfunction "POWER_GOOD_6") (pintype "passive"))
    )
    (net (code "88") (name "unconnected-(M1-PSV{slash}PSS-Pad4)") (class "Default")
      (node (ref "M1") (pin "4") (pinfunction "PSV/PSS_4") (pintype "passive"))
    )
    (net (code "89") (name "unconnected-(M1-REMOTE-Pad3)") (class "Default")
      (node (ref "M1") (pin "3") (pinfunction "REMOTE_3") (pintype "passive"))
    )
    (net (code "90") (name "unconnected-(U1-PA8-Pad29)") (class "Default")
      (node (ref "U1") (pin "29") (pinfunction "PA8_29") (pintype "bidirectional"))
    )
    (net (code "91") (name "unconnected-(U1-PA11-Pad32)") (class "Default")
      (node (ref "U1") (pin "32") (pinfunction "PA11_32") (pintype "bidirectional"))
    )
    (net (code "92") (name "unconnected-(U1-PA12-Pad33)") (class "Default")
      (node (ref "U1") (pin "33") (pinfunction "PA12_33") (pintype "bidirectional"))
    )
    (net (code "93") (name "unconnected-(U1-PA15{slash}JTDI-Pad38)") (class "Default")
      (node (ref "U1") (pin "38") (pinfunction "PA15/JTDI_38") (pintype "bidirectional"))
    )
    (net (code "94") (name "unconnected-(U1-PB3{slash}JTDO-Pad39)") (class "Default")
      (node (ref "U1") (pin "39") (pinfunction "PB3/JTDO_39") (pintype "bidirectional"))
    )
    (net (code "95") (name "unconnected-(U1-PB4{slash}JNTRST-Pad40)") (class "Default")
      (node (ref "U1") (pin "40") (pinfunction "PB4/JNTRST_40") (pintype "bidirectional"))
    )
    (net (code "96") (name "unconnected-(U1-PB5-Pad41)") (class "Default")
      (node (ref "U1") (pin "41") (pinfunction "PB5_41") (pintype "bidirectional"))
    )
    (net (code "97") (name "unconnected-(U1-PB8-Pad45)") (class "Default")
      (node (ref "U1") (pin "45") (pinfunction "PB8_45") (pintype "bidirectional"))
    )
    (net (code "98") (name "unconnected-(U1-PB9-Pad46)") (class "Default")
      (node (ref "U1") (pin "46") (pinfunction "PB9_46") (pintype "bidirectional"))
    )
    (net (code "99") (name "unconnected-(U1-PB12-Pad25)") (class "Default")
      (node (ref "U1") (pin "25") (pinfunction "PB12_25") (pintype "bidirectional"))
    )
    (net (code "100") (name "unconnected-(U1-PB13-Pad26)") (class "Default")
      (node (ref "U1") (pin "26") (pinfunction "PB13_26") (pintype "bidirectional"))
    )
    (net (code "101") (name "unconnected-(U1-PB14-Pad27)") (class "Default")
      (node (ref "U1") (pin "27") (pinfunction "PB14_27") (pintype "bidirectional"))
    )
    (net (code "102") (name "unconnected-(U1-PB15-Pad28)") (class "Default")
      (node (ref "U1") (pin "28") (pinfunction "PB15_28") (pintype "bidirectional"))
    )
    (net (code "103") (name "unconnected-(U1-PC13-TAMPER-RTC-Pad2)") (class "Default")
      (node (ref "U1") (pin "2") (pinfunction "PC13-TAMPER-RTC_2") (pintype "bidirectional"))
    )
    (net (code "104") (name "unconnected-(U1-PC14-OSC32_IN-Pad3)") (class "Default")
      (node (ref "U1") (pin "3") (pinfunction "PC14-OSC32_IN_3") (pintype "bidirectional"))
    )
    (net (code "105") (name "unconnected-(U1-PC15-OSC32_OUT-Pad4)") (class "Default")
      (node (ref "U1") (pin "4") (pinfunction "PC15-OSC32_OUT_4") (pintype "bidirectional"))
    )
    (net (code "106") (name "unconnected-(U1-VBAT-Pad1)") (class "Default")
      (node (ref "U1") (pin "1") (pinfunction "VBAT_1") (pintype "power_in"))
    )
  )
)
